# c150_rev_a.net
KiCad netlist of a schematic drawn in EAGLE
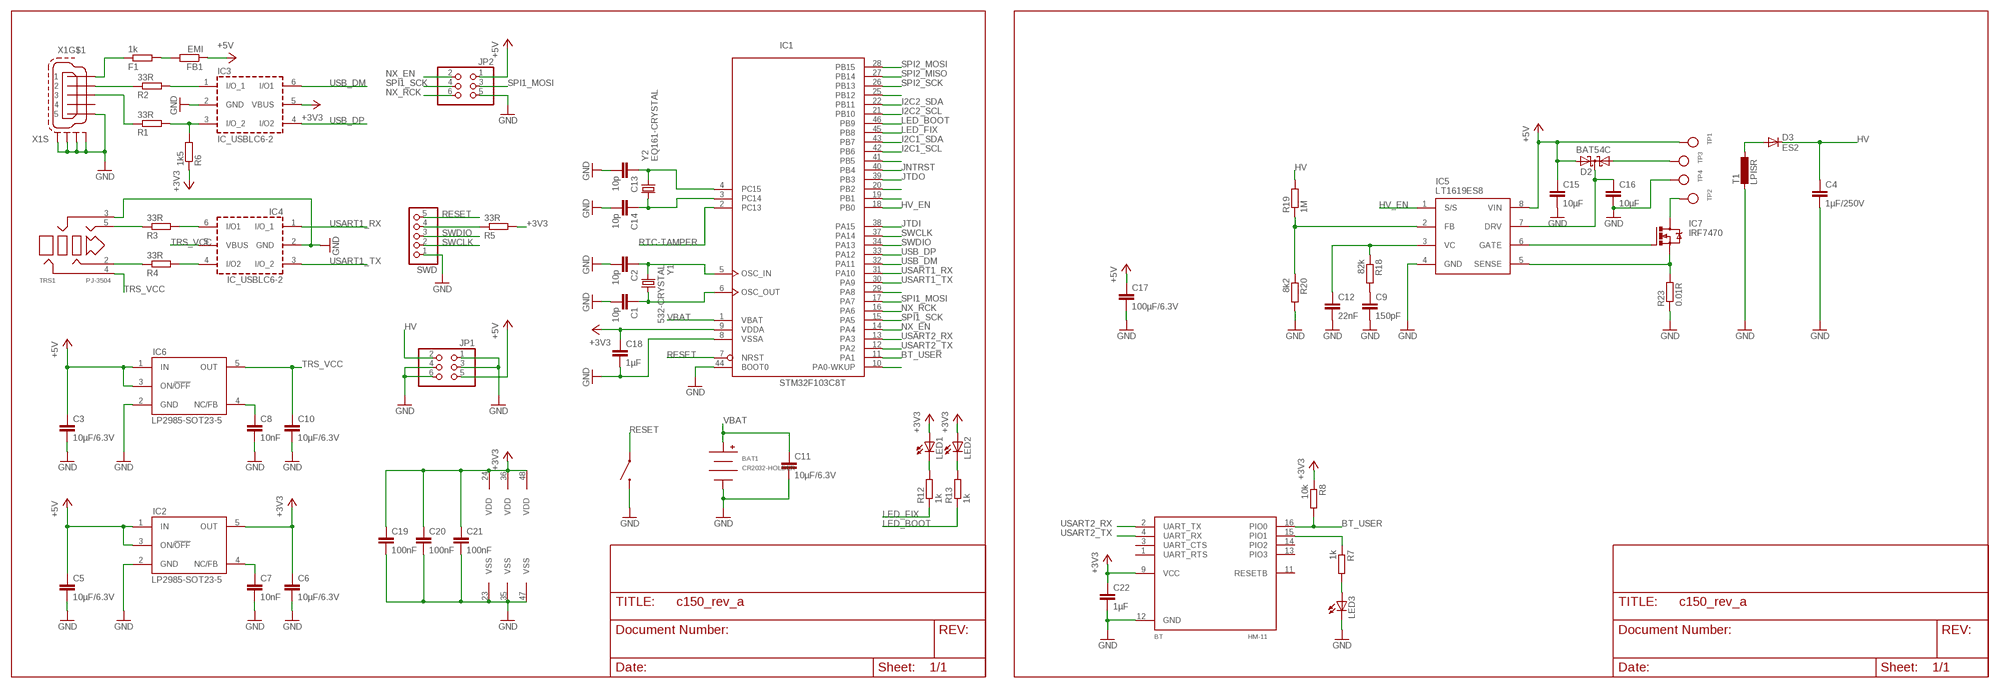
[diagram p0: schematic, sheet 1]

(export (version "E")
  (design (tool "Eeschema 10.0.6"))
  (components
    (comp (ref "BAT1")
      (value "CR2032-HOLDER")
      (footprint "eagle-import:CH28-2032LF")
      (libsource (lib "eagle-import") (part "CR2032-HOLDER"))
    )
    (comp (ref "BT")
      (value "HM-11")
      (footprint "eagle-import:HM-11")
      (libsource (lib "eagle-import") (part "HM-11"))
    )
    (comp (ref "C1")
      (value "10p")
      (footprint "eagle-import:C0603")
      (libsource (lib "eagle-import") (part "C-EUC0603"))
    )
    (comp (ref "C2")
      (value "10p")
      (footprint "eagle-import:C0603")
      (libsource (lib "eagle-import") (part "C-EUC0603"))
    )
    (comp (ref "C3")
      (value "10µF/6.3V")
      (footprint "eagle-import:C0603")
      (libsource (lib "eagle-import") (part "C-EUC0603"))
    )
    (comp (ref "C4")
      (value "1µF/250V")
      (footprint "eagle-import:C2220K")
      (libsource (lib "eagle-import") (part "C-EUC2220K"))
    )
    (comp (ref "C5")
      (value "10µF/6.3V")
      (footprint "eagle-import:C0603")
      (libsource (lib "eagle-import") (part "C-EUC0603"))
    )
    (comp (ref "C6")
      (value "10µF/6.3V")
      (footprint "eagle-import:C0603")
      (libsource (lib "eagle-import") (part "C-EUC0603"))
    )
    (comp (ref "C7")
      (value "10nF")
      (footprint "eagle-import:C0603")
      (libsource (lib "eagle-import") (part "C-EUC0603"))
    )
    (comp (ref "C8")
      (value "10nF")
      (footprint "eagle-import:C0603")
      (libsource (lib "eagle-import") (part "C-EUC0603"))
    )
    (comp (ref "C9")
      (value "150pF")
      (footprint "eagle-import:C0603")
      (libsource (lib "eagle-import") (part "C-EUC0603"))
    )
    (comp (ref "C10")
      (value "10µF/6.3V")
      (footprint "eagle-import:C0603")
      (libsource (lib "eagle-import") (part "C-EUC0603"))
    )
    (comp (ref "C11")
      (value "10µF/6.3V")
      (footprint "eagle-import:C0603")
      (libsource (lib "eagle-import") (part "C-EUC0603"))
    )
    (comp (ref "C12")
      (value "22nF")
      (footprint "eagle-import:C0603")
      (libsource (lib "eagle-import") (part "C-EUC0603"))
    )
    (comp (ref "C13")
      (value "10p")
      (footprint "eagle-import:C0603")
      (libsource (lib "eagle-import") (part "C-EUC0603"))
    )
    (comp (ref "C14")
      (value "10p")
      (footprint "eagle-import:C0603")
      (libsource (lib "eagle-import") (part "C-EUC0603"))
    )
    (comp (ref "C15")
      (value "10µF")
      (footprint "eagle-import:C0603")
      (libsource (lib "eagle-import") (part "C-EUC0603"))
    )
    (comp (ref "C16")
      (value "10µF")
      (footprint "eagle-import:C0603")
      (libsource (lib "eagle-import") (part "C-EUC0603"))
    )
    (comp (ref "C17")
      (value "100µF/6.3V")
      (footprint "eagle-import:C1210")
      (libsource (lib "eagle-import") (part "C-EUC1210"))
    )
    (comp (ref "C18")
      (value "1µF")
      (footprint "eagle-import:C0603")
      (libsource (lib "eagle-import") (part "C-EUC0603"))
    )
    (comp (ref "C19")
      (value "100nF")
      (footprint "eagle-import:C0603")
      (libsource (lib "eagle-import") (part "C-EUC0603"))
    )
    (comp (ref "C20")
      (value "100nF")
      (footprint "eagle-import:C0603")
      (libsource (lib "eagle-import") (part "C-EUC0603"))
    )
    (comp (ref "C21")
      (value "100nF")
      (footprint "eagle-import:C0603")
      (libsource (lib "eagle-import") (part "C-EUC0603"))
    )
    (comp (ref "C22")
      (value "1µF")
      (footprint "eagle-import:C0603")
      (libsource (lib "eagle-import") (part "C-EUC0603"))
    )
    (comp (ref "D2")
      (value "BAT54C")
      (footprint "eagle-import:SOT23")
      (libsource (lib "eagle-import") (part "BAT54C"))
    )
    (comp (ref "D3")
      (value "ES2")
      (footprint "eagle-import:DO-214AA")
      (libsource (lib "eagle-import") (part "ES2"))
    )
    (comp (ref "F1")
      (value "1k")
      (footprint "eagle-import:R0603")
      (libsource (lib "eagle-import") (part "R-EU_R0603"))
    )
    (comp (ref "FB1")
      (value "EMI")
      (footprint "eagle-import:R0603")
      (libsource (lib "eagle-import") (part "R-EU_R0603"))
    )
    (comp (ref "IC1")
      (value "STM32F103C8T")
      (footprint "eagle-import:LQFP48")
      (libsource (lib "eagle-import") (part "STM32F103CT8"))
    )
    (comp (ref "IC2")
      (value "LP2985-SOT23-5")
      (footprint "eagle-import:SOT23-5")
      (libsource (lib "eagle-import") (part "LP2985-SOT23-5"))
    )
    (comp (ref "IC3")
      (value "IC_USBLC6-2")
      (footprint "eagle-import:SOT-23-6L")
      (libsource (lib "eagle-import") (part "IC_USBLC6-2"))
    )
    (comp (ref "IC4")
      (value "IC_USBLC6-2")
      (footprint "eagle-import:SOT-23-6L")
      (libsource (lib "eagle-import") (part "IC_USBLC6-2"))
    )
    (comp (ref "IC5")
      (value "LT1619ES8")
      (footprint "eagle-import:SO8")
      (libsource (lib "eagle-import") (part "LT1619ES8"))
    )
    (comp (ref "IC6")
      (value "LP2985-SOT23-5")
      (footprint "eagle-import:SOT23-5")
      (libsource (lib "eagle-import") (part "LP2985-SOT23-5"))
    )
    (comp (ref "IC7")
      (value "IRF7470")
      (footprint "eagle-import:SO8")
      (libsource (lib "eagle-import") (part "IRF7470"))
    )
    (comp (ref "ISP")
      (value "TACT-SWITCH-40-40")
      (footprint "eagle-import:40-40")
      (libsource (lib "eagle-import") (part "TACT-SWITCH-40-40"))
    )
    (comp (ref "JP1")
      (value "PINHD-2X3_2.54-SMD")
      (footprint "eagle-import:2X03SMD")
      (libsource (lib "eagle-import") (part "PINHD-2X3_2.54-SMD"))
    )
    (comp (ref "JP2")
      (value "PINHD-2X3_2.54-SMD")
      (footprint "eagle-import:2X03SMD")
      (libsource (lib "eagle-import") (part "PINHD-2X3_2.54-SMD"))
    )
    (comp (ref "LED1")
      (value "LEDCHIP-LED0603")
      (footprint "eagle-import:CHIP-LED0603")
      (libsource (lib "eagle-import") (part "LEDCHIP-LED0603"))
    )
    (comp (ref "LED2")
      (value "LEDCHIP-LED0603")
      (footprint "eagle-import:CHIP-LED0603")
      (libsource (lib "eagle-import") (part "LEDCHIP-LED0603"))
    )
    (comp (ref "LED3")
      (value "LEDCHIP-LED0603")
      (footprint "eagle-import:CHIP-LED0603")
      (libsource (lib "eagle-import") (part "LEDCHIP-LED0603"))
    )
    (comp (ref "R1")
      (value "33R")
      (footprint "eagle-import:R0603")
      (libsource (lib "eagle-import") (part "R-EU_R0603"))
    )
    (comp (ref "R2")
      (value "33R")
      (footprint "eagle-import:R0603")
      (libsource (lib "eagle-import") (part "R-EU_R0603"))
    )
    (comp (ref "R3")
      (value "33R")
      (footprint "eagle-import:R0603")
      (libsource (lib "eagle-import") (part "R-EU_R0603"))
    )
    (comp (ref "R4")
      (value "33R")
      (footprint "eagle-import:R0603")
      (libsource (lib "eagle-import") (part "R-EU_R0603"))
    )
    (comp (ref "R5")
      (value "33R")
      (footprint "eagle-import:R0603")
      (libsource (lib "eagle-import") (part "R-EU_R0603"))
    )
    (comp (ref "R6")
      (value "1k5")
      (footprint "eagle-import:R0603")
      (libsource (lib "eagle-import") (part "R-EU_R0603"))
    )
    (comp (ref "R7")
      (value "1k")
      (footprint "eagle-import:R0603")
      (libsource (lib "eagle-import") (part "R-EU_R0603"))
    )
    (comp (ref "R8")
      (value "10k")
      (footprint "eagle-import:R0603")
      (libsource (lib "eagle-import") (part "R-EU_R0603"))
    )
    (comp (ref "R12")
      (value "1k")
      (footprint "eagle-import:R0603")
      (libsource (lib "eagle-import") (part "R-EU_R0603"))
    )
    (comp (ref "R13")
      (value "1k")
      (footprint "eagle-import:R0603")
      (libsource (lib "eagle-import") (part "R-EU_R0603"))
    )
    (comp (ref "R18")
      (value "82k")
      (footprint "eagle-import:R0603")
      (libsource (lib "eagle-import") (part "R-EU_R0603"))
    )
    (comp (ref "R19")
      (value "1M")
      (footprint "eagle-import:M1206")
      (libsource (lib "eagle-import") (part "R-EU_M1206"))
    )
    (comp (ref "R20")
      (value "8k2")
      (footprint "eagle-import:R0603")
      (libsource (lib "eagle-import") (part "R-EU_R0603"))
    )
    (comp (ref "R23")
      (value "0.01R")
      (footprint "eagle-import:R1206")
      (libsource (lib "eagle-import") (part "R-EU_R1206"))
    )
    (comp (ref "SWD")
      (value "HEADER-1X5ROUND")
      (footprint "eagle-import:1X05_ROUND")
      (libsource (lib "eagle-import") (part "HEADER-1X5ROUND"))
    )
    (comp (ref "T1")
      (value "LPISR")
      (footprint "eagle-import:PISR")
      (libsource (lib "eagle-import") (part "LPISR"))
    )
    (comp (ref "TP1")
      (value "TESTPOINTROUND2MM")
      (footprint "eagle-import:TESTPOINT_ROUND_2MM")
      (libsource (lib "eagle-import") (part "TESTPOINTROUND2MM"))
    )
    (comp (ref "TP2")
      (value "TESTPOINTROUND2MM")
      (footprint "eagle-import:TESTPOINT_ROUND_2MM")
      (libsource (lib "eagle-import") (part "TESTPOINTROUND2MM"))
    )
    (comp (ref "TP3")
      (value "TESTPOINTROUND2MM")
      (footprint "eagle-import:TESTPOINT_ROUND_2MM")
      (libsource (lib "eagle-import") (part "TESTPOINTROUND2MM"))
    )
    (comp (ref "TP4")
      (value "TESTPOINTROUND2MM")
      (footprint "eagle-import:TESTPOINT_ROUND_2MM")
      (libsource (lib "eagle-import") (part "TESTPOINTROUND2MM"))
    )
    (comp (ref "TRS1")
      (value "PJ-3504")
      (footprint "eagle-import:YD-PJ-3504")
      (libsource (lib "eagle-import") (part "PJ-3504"))
    )
    (comp (ref "X1")
      (value "MINI-USB-SCHIELD-32005-201")
      (footprint "eagle-import:32005-201")
      (libsource (lib "eagle-import") (part "MINI-USB-SCHIELD-32005-201"))
    )
    (comp (ref "Y1")
      (value "532-CRYSTAL")
      (footprint "eagle-import:2PIN50X32")
      (libsource (lib "eagle-import") (part "532-CRYSTAL"))
    )
    (comp (ref "Y2")
      (value "EQ161-CRYSTAL")
      (footprint "eagle-import:EQ161")
      (libsource (lib "eagle-import") (part "EQ161-CRYSTAL"))
    )
  )
  (nets
    (net (code "1") (name "+3V3") (class "Default")
      (node (ref "BT") (pin "9") (pinfunction "VCC_9") (pintype "bidirectional"))
      (node (ref "C18") (pin "1") (pinfunction "1_1") (pintype "passive"))
      (node (ref "C19") (pin "1") (pinfunction "1_1") (pintype "passive"))
      (node (ref "C20") (pin "1") (pinfunction "1_1") (pintype "passive"))
      (node (ref "C21") (pin "1") (pinfunction "1_1") (pintype "passive"))
      (node (ref "C22") (pin "1") (pinfunction "1_1") (pintype "passive"))
      (node (ref "C6") (pin "1") (pinfunction "1_1") (pintype "passive"))
      (node (ref "IC1") (pin "24") (pinfunction "VDD_24") (pintype "power_in"))
      (node (ref "IC1") (pin "36") (pinfunction "VDD_36") (pintype "power_in"))
      (node (ref "IC1") (pin "48") (pinfunction "VDD_48") (pintype "power_in"))
      (node (ref "IC1") (pin "9") (pinfunction "VDDA_9") (pintype "power_in"))
      (node (ref "IC2") (pin "5") (pinfunction "OUT_5") (pintype "bidirectional"))
      (node (ref "IC3") (pin "5") (pinfunction "VBUS_5") (pintype "bidirectional"))
      (node (ref "LED1") (pin "A") (pinfunction "A_A") (pintype "passive"))
      (node (ref "LED2") (pin "A") (pinfunction "A_A") (pintype "passive"))
      (node (ref "R5") (pin "2") (pinfunction "2_2") (pintype "passive"))
      (node (ref "R6") (pin "1") (pinfunction "1_1") (pintype "passive"))
      (node (ref "R8") (pin "1") (pinfunction "1_1") (pintype "passive"))
    )
    (net (code "2") (name "+5V") (class "Default")
      (node (ref "C15") (pin "1") (pinfunction "1_1") (pintype "passive"))
      (node (ref "C17") (pin "1") (pinfunction "1_1") (pintype "passive"))
      (node (ref "C3") (pin "1") (pinfunction "1_1") (pintype "passive"))
      (node (ref "C5") (pin "1") (pinfunction "1_1") (pintype "passive"))
      (node (ref "D2") (pin "2") (pinfunction "A2_2") (pintype "passive"))
      (node (ref "FB1") (pin "1") (pinfunction "1_1") (pintype "passive"))
      (node (ref "IC2") (pin "1") (pinfunction "IN_1") (pintype "bidirectional"))
      (node (ref "IC2") (pin "3") (pinfunction "ON/~{OFF}_3") (pintype "bidirectional"))
      (node (ref "IC5") (pin "8") (pinfunction "VIN_8") (pintype "bidirectional"))
      (node (ref "IC6") (pin "1") (pinfunction "IN_1") (pintype "bidirectional"))
      (node (ref "IC6") (pin "3") (pinfunction "ON/~{OFF}_3") (pintype "bidirectional"))
      (node (ref "JP1") (pin "5") (pinfunction "5_5") (pintype "passive"))
      (node (ref "JP2") (pin "1") (pinfunction "1_1") (pintype "passive"))
      (node (ref "TP1") (pin "P$1") (pinfunction "P$1_P$1") (pintype "bidirectional"))
    )
    (net (code "3") (name "/BT_USER") (class "Default")
      (node (ref "BT") (pin "16") (pinfunction "PIO0_16") (pintype "bidirectional"))
      (node (ref "IC1") (pin "11") (pinfunction "PA1_11") (pintype "bidirectional"))
      (node (ref "R8") (pin "2") (pinfunction "2_2") (pintype "passive"))
    )
    (net (code "4") (name "/HV") (class "Default")
      (node (ref "C4") (pin "1") (pinfunction "1_1") (pintype "passive"))
      (node (ref "D3") (pin "C") (pinfunction "C_C") (pintype "passive"))
      (node (ref "JP1") (pin "2") (pinfunction "2_2") (pintype "passive"))
      (node (ref "R19") (pin "2") (pinfunction "2_2") (pintype "passive"))
    )
    (net (code "5") (name "/HV_EN") (class "Default")
      (node (ref "IC1") (pin "18") (pinfunction "PB0_18") (pintype "bidirectional"))
      (node (ref "IC5") (pin "1") (pinfunction "S/S_1") (pintype "bidirectional"))
    )
    (net (code "6") (name "/I2C1_SCL") (class "Default")
      (node (ref "IC1") (pin "42") (pinfunction "PB6_42") (pintype "bidirectional"))
    )
    (net (code "7") (name "/I2C1_SDA") (class "Default")
      (node (ref "IC1") (pin "43") (pinfunction "PB7_43") (pintype "bidirectional"))
    )
    (net (code "8") (name "/I2C2_SCL") (class "Default")
      (node (ref "IC1") (pin "21") (pinfunction "PB10_21") (pintype "bidirectional"))
    )
    (net (code "9") (name "/I2C2_SDA") (class "Default")
      (node (ref "IC1") (pin "22") (pinfunction "PB11_22") (pintype "bidirectional"))
    )
    (net (code "10") (name "/JNTRST") (class "Default")
      (node (ref "IC1") (pin "40") (pinfunction "PB4_40") (pintype "bidirectional"))
    )
    (net (code "11") (name "/JTDI") (class "Default")
      (node (ref "IC1") (pin "38") (pinfunction "PA15_38") (pintype "bidirectional"))
    )
    (net (code "12") (name "/JTDO") (class "Default")
      (node (ref "IC1") (pin "39") (pinfunction "PB3_39") (pintype "bidirectional"))
    )
    (net (code "13") (name "/LED_BOOT") (class "Default")
      (node (ref "IC1") (pin "46") (pinfunction "PB9_46") (pintype "bidirectional"))
      (node (ref "R13") (pin "1") (pinfunction "1_1") (pintype "passive"))
    )
    (net (code "14") (name "/LED_FIX") (class "Default")
      (node (ref "IC1") (pin "45") (pinfunction "PB8_45") (pintype "bidirectional"))
      (node (ref "R12") (pin "1") (pinfunction "1_1") (pintype "passive"))
    )
    (net (code "15") (name "/NX_EN") (class "Default")
      (node (ref "IC1") (pin "14") (pinfunction "PA4_14") (pintype "bidirectional"))
      (node (ref "JP2") (pin "2") (pinfunction "2_2") (pintype "passive"))
    )
    (net (code "16") (name "/NX_RCK") (class "Default")
      (node (ref "IC1") (pin "16") (pinfunction "PA6_16") (pintype "bidirectional"))
      (node (ref "JP2") (pin "6") (pinfunction "6_6") (pintype "passive"))
    )
    (net (code "17") (name "/RESET") (class "Default")
      (node (ref "IC1") (pin "7") (pinfunction "NRST_7") (pintype "bidirectional"))
      (node (ref "ISP") (pin "3") (pinfunction "P$2_3") (pintype "bidirectional"))
      (node (ref "ISP") (pin "4") (pinfunction "P$2_4") (pintype "bidirectional"))
      (node (ref "SWD") (pin "5") (pinfunction "5_5") (pintype "passive"))
    )
    (net (code "18") (name "/RTC-TAMPER") (class "Default")
      (node (ref "IC1") (pin "2") (pinfunction "PC13_2") (pintype "bidirectional"))
    )
    (net (code "19") (name "/SPI1_MOSI") (class "Default")
      (node (ref "IC1") (pin "17") (pinfunction "PA7_17") (pintype "bidirectional"))
      (node (ref "JP2") (pin "3") (pinfunction "3_3") (pintype "passive"))
    )
    (net (code "20") (name "/SPI1_SCK") (class "Default")
      (node (ref "IC1") (pin "15") (pinfunction "PA5_15") (pintype "bidirectional"))
      (node (ref "JP2") (pin "4") (pinfunction "4_4") (pintype "passive"))
    )
    (net (code "21") (name "/SPI2_MISO") (class "Default")
      (node (ref "IC1") (pin "27") (pinfunction "PB14_27") (pintype "bidirectional"))
    )
    (net (code "22") (name "/SPI2_MOSI") (class "Default")
      (node (ref "IC1") (pin "28") (pinfunction "PB15_28") (pintype "bidirectional"))
    )
    (net (code "23") (name "/SPI2_SCK") (class "Default")
      (node (ref "IC1") (pin "26") (pinfunction "PB13_26") (pintype "bidirectional"))
    )
    (net (code "24") (name "/SWCLK") (class "Default")
      (node (ref "IC1") (pin "37") (pinfunction "PA14_37") (pintype "bidirectional"))
      (node (ref "SWD") (pin "2") (pinfunction "2_2") (pintype "passive"))
    )
    (net (code "25") (name "/SWDIO") (class "Default")
      (node (ref "IC1") (pin "34") (pinfunction "PA13_34") (pintype "bidirectional"))
      (node (ref "SWD") (pin "3") (pinfunction "3_3") (pintype "passive"))
    )
    (net (code "26") (name "/TRS_VCC") (class "Default")
      (node (ref "C10") (pin "1") (pinfunction "1_1") (pintype "passive"))
      (node (ref "IC4") (pin "5") (pinfunction "VBUS_5") (pintype "bidirectional"))
      (node (ref "IC6") (pin "5") (pinfunction "OUT_5") (pintype "bidirectional"))
      (node (ref "TRS1") (pin "4") (pinfunction "4_4") (pintype "bidirectional"))
    )
    (net (code "27") (name "/USART1_RX") (class "Default")
      (node (ref "IC1") (pin "31") (pinfunction "PA10_31") (pintype "bidirectional"))
      (node (ref "IC4") (pin "1") (pinfunction "I/O_1_1") (pintype "bidirectional"))
    )
    (net (code "28") (name "/USART1_TX") (class "Default")
      (node (ref "IC1") (pin "30") (pinfunction "PA9_30") (pintype "bidirectional"))
      (node (ref "IC4") (pin "3") (pinfunction "I/O_2_3") (pintype "bidirectional"))
    )
    (net (code "29") (name "/USART2_RX") (class "Default")
      (node (ref "BT") (pin "2") (pinfunction "UART_TX_2") (pintype "bidirectional"))
      (node (ref "IC1") (pin "13") (pinfunction "PA3_13") (pintype "bidirectional"))
    )
    (net (code "30") (name "/USART2_TX") (class "Default")
      (node (ref "BT") (pin "4") (pinfunction "UART_RX_4") (pintype "bidirectional"))
      (node (ref "IC1") (pin "12") (pinfunction "PA2_12") (pintype "bidirectional"))
    )
    (net (code "31") (name "/USB_DM") (class "Default")
      (node (ref "IC1") (pin "32") (pinfunction "PA11_32") (pintype "bidirectional"))
      (node (ref "IC3") (pin "6") (pinfunction "I/O1_6") (pintype "bidirectional"))
    )
    (net (code "32") (name "/USB_DP") (class "Default")
      (node (ref "IC1") (pin "33") (pinfunction "PA12_33") (pintype "bidirectional"))
      (node (ref "IC3") (pin "4") (pinfunction "I/O2_4") (pintype "bidirectional"))
    )
    (net (code "33") (name "/VBAT") (class "Default")
      (node (ref "BAT1") (pin "POS") (pinfunction "POS_POS") (pintype "bidirectional"))
      (node (ref "C11") (pin "1") (pinfunction "1_1") (pintype "passive"))
      (node (ref "IC1") (pin "1") (pinfunction "VBAT_1") (pintype "power_in"))
    )
    (net (code "34") (name "GND") (class "Default")
      (node (ref "BAT1") (pin "NEG") (pinfunction "NEG_NEG") (pintype "bidirectional"))
      (node (ref "BT") (pin "12") (pinfunction "GND_12") (pintype "bidirectional"))
      (node (ref "C1") (pin "2") (pinfunction "2_2") (pintype "passive"))
      (node (ref "C10") (pin "2") (pinfunction "2_2") (pintype "passive"))
      (node (ref "C11") (pin "2") (pinfunction "2_2") (pintype "passive"))
      (node (ref "C12") (pin "2") (pinfunction "2_2") (pintype "passive"))
      (node (ref "C13") (pin "2") (pinfunction "2_2") (pintype "passive"))
      (node (ref "C14") (pin "2") (pinfunction "2_2") (pintype "passive"))
      (node (ref "C15") (pin "2") (pinfunction "2_2") (pintype "passive"))
      (node (ref "C16") (pin "2") (pinfunction "2_2") (pintype "passive"))
      (node (ref "C17") (pin "2") (pinfunction "2_2") (pintype "passive"))
      (node (ref "C18") (pin "2") (pinfunction "2_2") (pintype "passive"))
      (node (ref "C19") (pin "2") (pinfunction "2_2") (pintype "passive"))
      (node (ref "C2") (pin "2") (pinfunction "2_2") (pintype "passive"))
      (node (ref "C20") (pin "2") (pinfunction "2_2") (pintype "passive"))
      (node (ref "C21") (pin "2") (pinfunction "2_2") (pintype "passive"))
      (node (ref "C22") (pin "2") (pinfunction "2_2") (pintype "passive"))
      (node (ref "C3") (pin "2") (pinfunction "2_2") (pintype "passive"))
      (node (ref "C4") (pin "2") (pinfunction "2_2") (pintype "passive"))
      (node (ref "C5") (pin "2") (pinfunction "2_2") (pintype "passive"))
      (node (ref "C6") (pin "2") (pinfunction "2_2") (pintype "passive"))
      (node (ref "C7") (pin "2") (pinfunction "2_2") (pintype "passive"))
      (node (ref "C8") (pin "2") (pinfunction "2_2") (pintype "passive"))
      (node (ref "C9") (pin "2") (pinfunction "2_2") (pintype "passive"))
      (node (ref "IC1") (pin "23") (pinfunction "VSS_23") (pintype "power_in"))
      (node (ref "IC1") (pin "35") (pinfunction "VSS_35") (pintype "power_in"))
      (node (ref "IC1") (pin "44") (pinfunction "BOOT0_44") (pintype "input"))
      (node (ref "IC1") (pin "47") (pinfunction "VSS_47") (pintype "power_in"))
      (node (ref "IC1") (pin "8") (pinfunction "VSSA_8") (pintype "power_in"))
      (node (ref "IC2") (pin "2") (pinfunction "GND_2") (pintype "bidirectional"))
      (node (ref "IC3") (pin "2") (pinfunction "GND_2") (pintype "bidirectional"))
      (node (ref "IC4") (pin "2") (pinfunction "GND_2") (pintype "bidirectional"))
      (node (ref "IC5") (pin "4") (pinfunction "GND_4") (pintype "bidirectional"))
      (node (ref "IC6") (pin "2") (pinfunction "GND_2") (pintype "bidirectional"))
      (node (ref "ISP") (pin "1") (pinfunction "P$1_1") (pintype "bidirectional"))
      (node (ref "ISP") (pin "2") (pinfunction "P$1_2") (pintype "bidirectional"))
      (node (ref "JP1") (pin "1") (pinfunction "1_1") (pintype "passive"))
      (node (ref "JP1") (pin "3") (pinfunction "3_3") (pintype "passive"))
      (node (ref "JP1") (pin "4") (pinfunction "4_4") (pintype "passive"))
      (node (ref "JP1") (pin "6") (pinfunction "6_6") (pintype "passive"))
      (node (ref "JP2") (pin "5") (pinfunction "5_5") (pintype "passive"))
      (node (ref "LED3") (pin "C") (pinfunction "C_C") (pintype "passive"))
      (node (ref "R20") (pin "2") (pinfunction "2_2") (pintype "passive"))
      (node (ref "R23") (pin "1") (pinfunction "1_1") (pintype "passive"))
      (node (ref "SWD") (pin "1") (pinfunction "1_1") (pintype "passive"))
      (node (ref "T1") (pin "P$2") (pinfunction "2_P$2") (pintype "passive"))
      (node (ref "TP4") (pin "P$1") (pinfunction "P$1_P$1") (pintype "bidirectional"))
      (node (ref "TRS1") (pin "3") (pinfunction "3_3") (pintype "bidirectional"))
      (node (ref "X1") (pin "5") (pinfunction "5_5") (pintype "passive"))
      (node (ref "X1") (pin "M1") (pinfunction "S1_M1") (pintype "passive"))
      (node (ref "X1") (pin "M2") (pinfunction "S2_M2") (pintype "passive"))
      (node (ref "X1") (pin "M3") (pinfunction "S3_M3") (pintype "passive"))
      (node (ref "X1") (pin "M4") (pinfunction "S4_M4") (pintype "passive"))
    )
    (net (code "35") (name "Net-(BT-PIO1)") (class "Default")
      (node (ref "BT") (pin "15") (pinfunction "PIO1_15") (pintype "bidirectional"))
      (node (ref "R7") (pin "1") (pinfunction "1_1") (pintype "passive"))
    )
    (net (code "36") (name "Net-(C9-Pad1)") (class "Default")
      (node (ref "C9") (pin "1") (pinfunction "1_1") (pintype "passive"))
      (node (ref "R18") (pin "2") (pinfunction "2_2") (pintype "passive"))
    )
    (net (code "37") (name "Net-(D2-A1)") (class "Default")
      (node (ref "D2") (pin "1") (pinfunction "A1_1") (pintype "passive"))
      (node (ref "TP3") (pin "P$1") (pinfunction "P$1_P$1") (pintype "bidirectional"))
    )
    (net (code "38") (name "Net-(D2-CC)") (class "Default")
      (node (ref "C16") (pin "1") (pinfunction "1_1") (pintype "passive"))
      (node (ref "D2") (pin "3") (pinfunction "CC_3") (pintype "passive"))
      (node (ref "IC5") (pin "7") (pinfunction "DRV_7") (pintype "bidirectional"))
    )
    (net (code "39") (name "Net-(F1-Pad1)") (class "Default")
      (node (ref "F1") (pin "1") (pinfunction "1_1") (pintype "passive"))
      (node (ref "X1") (pin "1") (pinfunction "1_1") (pintype "passive"))
    )
    (net (code "40") (name "Net-(F1-Pad2)") (class "Default")
      (node (ref "F1") (pin "2") (pinfunction "2_2") (pintype "passive"))
      (node (ref "FB1") (pin "2") (pinfunction "2_2") (pintype "passive"))
    )
    (net (code "41") (name "Net-(IC1A-OSC_IN)") (class "Default")
      (node (ref "C2") (pin "1") (pinfunction "1_1") (pintype "passive"))
      (node (ref "IC1") (pin "5") (pinfunction "OSC_IN_5") (pintype "bidirectional"))
      (node (ref "Y1") (pin "P$2") (pinfunction "2_P$2") (pintype "passive"))
    )
    (net (code "42") (name "Net-(IC1A-OSC_OUT)") (class "Default")
      (node (ref "C1") (pin "1") (pinfunction "1_1") (pintype "passive"))
      (node (ref "IC1") (pin "6") (pinfunction "OSC_OUT_6") (pintype "bidirectional"))
      (node (ref "Y1") (pin "P$1") (pinfunction "1_P$1") (pintype "passive"))
    )
    (net (code "43") (name "Net-(IC1A-PC14)") (class "Default")
      (node (ref "C14") (pin "1") (pinfunction "1_1") (pintype "passive"))
      (node (ref "IC1") (pin "3") (pinfunction "PC14_3") (pintype "bidirectional"))
      (node (ref "Y2") (pin "P$2") (pinfunction "2_P$2") (pintype "passive"))
    )
    (net (code "44") (name "Net-(IC1A-PC15)") (class "Default")
      (node (ref "C13") (pin "1") (pinfunction "1_1") (pintype "passive"))
      (node (ref "IC1") (pin "4") (pinfunction "PC15_4") (pintype "bidirectional"))
      (node (ref "Y2") (pin "P$1") (pinfunction "1_P$1") (pintype "passive"))
    )
    (net (code "45") (name "Net-(IC2-NC{slash}FB)") (class "Default")
      (node (ref "C7") (pin "1") (pinfunction "1_1") (pintype "passive"))
      (node (ref "IC2") (pin "4") (pinfunction "NC/FB_4") (pintype "bidirectional"))
    )
    (net (code "46") (name "Net-(IC3-I{slash}O_1)") (class "Default")
      (node (ref "IC3") (pin "1") (pinfunction "I/O_1_1") (pintype "bidirectional"))
      (node (ref "R2") (pin "2") (pinfunction "2_2") (pintype "passive"))
    )
    (net (code "47") (name "Net-(IC3-I{slash}O_2)") (class "Default")
      (node (ref "IC3") (pin "3") (pinfunction "I/O_2_3") (pintype "bidirectional"))
      (node (ref "R1") (pin "2") (pinfunction "2_2") (pintype "passive"))
      (node (ref "R6") (pin "2") (pinfunction "2_2") (pintype "passive"))
    )
    (net (code "48") (name "Net-(IC4-I{slash}O1)") (class "Default")
      (node (ref "IC4") (pin "6") (pinfunction "I/O1_6") (pintype "bidirectional"))
      (node (ref "R3") (pin "2") (pinfunction "2_2") (pintype "passive"))
    )
    (net (code "49") (name "Net-(IC4-I{slash}O2)") (class "Default")
      (node (ref "IC4") (pin "4") (pinfunction "I/O2_4") (pintype "bidirectional"))
      (node (ref "R4") (pin "2") (pinfunction "2_2") (pintype "passive"))
    )
    (net (code "50") (name "Net-(IC5-FB)") (class "Default")
      (node (ref "IC5") (pin "2") (pinfunction "FB_2") (pintype "bidirectional"))
      (node (ref "R19") (pin "1") (pinfunction "1_1") (pintype "passive"))
      (node (ref "R20") (pin "1") (pinfunction "1_1") (pintype "passive"))
    )
    (net (code "51") (name "Net-(IC5-GATE)") (class "Default")
      (node (ref "IC5") (pin "6") (pinfunction "GATE_6") (pintype "bidirectional"))
      (node (ref "IC7") (pin "4") (pinfunction "G_4") (pintype "passive"))
    )
    (net (code "52") (name "Net-(IC5-SENSE)") (class "Default")
      (node (ref "IC5") (pin "5") (pinfunction "SENSE_5") (pintype "bidirectional"))
      (node (ref "IC7") (pin "1") (pinfunction "S_1") (pintype "passive"))
      (node (ref "IC7") (pin "2") (pinfunction "S_2") (pintype "passive"))
      (node (ref "IC7") (pin "3") (pinfunction "S_3") (pintype "passive"))
      (node (ref "R23") (pin "2") (pinfunction "2_2") (pintype "passive"))
    )
    (net (code "53") (name "Net-(IC5-VC)") (class "Default")
      (node (ref "C12") (pin "1") (pinfunction "1_1") (pintype "passive"))
      (node (ref "IC5") (pin "3") (pinfunction "VC_3") (pintype "bidirectional"))
      (node (ref "R18") (pin "1") (pinfunction "1_1") (pintype "passive"))
    )
    (net (code "54") (name "Net-(IC6-NC{slash}FB)") (class "Default")
      (node (ref "C8") (pin "1") (pinfunction "1_1") (pintype "passive"))
      (node (ref "IC6") (pin "4") (pinfunction "NC/FB_4") (pintype "bidirectional"))
    )
    (net (code "55") (name "Net-(IC7-D-Pad5)") (class "Default")
      (node (ref "IC7") (pin "5") (pinfunction "D_5") (pintype "passive"))
      (node (ref "IC7") (pin "6") (pinfunction "D_6") (pintype "passive"))
      (node (ref "IC7") (pin "7") (pinfunction "D_7") (pintype "passive"))
      (node (ref "IC7") (pin "8") (pinfunction "D_8") (pintype "passive"))
      (node (ref "TP2") (pin "P$1") (pinfunction "P$1_P$1") (pintype "bidirectional"))
    )
    (net (code "56") (name "Net-(LED1-PadC)") (class "Default")
      (node (ref "LED1") (pin "C") (pinfunction "C_C") (pintype "passive"))
      (node (ref "R12") (pin "2") (pinfunction "2_2") (pintype "passive"))
    )
    (net (code "57") (name "Net-(LED2-PadC)") (class "Default")
      (node (ref "LED2") (pin "C") (pinfunction "C_C") (pintype "passive"))
      (node (ref "R13") (pin "2") (pinfunction "2_2") (pintype "passive"))
    )
    (net (code "58") (name "Net-(LED3-PadA)") (class "Default")
      (node (ref "LED3") (pin "A") (pinfunction "A_A") (pintype "passive"))
      (node (ref "R7") (pin "2") (pinfunction "2_2") (pintype "passive"))
    )
    (net (code "59") (name "Net-(R1-Pad1)") (class "Default")
      (node (ref "R1") (pin "1") (pinfunction "1_1") (pintype "passive"))
      (node (ref "X1") (pin "3") (pinfunction "3_3") (pintype "passive"))
    )
    (net (code "60") (name "Net-(R2-Pad1)") (class "Default")
      (node (ref "R2") (pin "1") (pinfunction "1_1") (pintype "passive"))
      (node (ref "X1") (pin "2") (pinfunction "2_2") (pintype "passive"))
    )
    (net (code "61") (name "Net-(R3-Pad1)") (class "Default")
      (node (ref "R3") (pin "1") (pinfunction "1_1") (pintype "passive"))
      (node (ref "TRS1") (pin "5") (pinfunction "5_5") (pintype "bidirectional"))
    )
    (net (code "62") (name "Net-(R4-Pad1)") (class "Default")
      (node (ref "R4") (pin "1") (pinfunction "1_1") (pintype "passive"))
      (node (ref "TRS1") (pin "2") (pinfunction "2_2") (pintype "bidirectional"))
    )
    (net (code "63") (name "Net-(R5-Pad1)") (class "Default")
      (node (ref "R5") (pin "1") (pinfunction "1_1") (pintype "passive"))
      (node (ref "SWD") (pin "4") (pinfunction "4_4") (pintype "passive"))
    )
    (net (code "64") (name "Net-(T1-1)") (class "Default")
      (node (ref "D3") (pin "A") (pinfunction "A_A") (pintype "passive"))
      (node (ref "T1") (pin "P$1") (pinfunction "1_P$1") (pintype "passive"))
    )
    (net (code "65") (name "unconnected-(BT-PIO2-Pad14)") (class "Default")
      (node (ref "BT") (pin "14") (pinfunction "PIO2_14") (pintype "bidirectional"))
    )
    (net (code "66") (name "unconnected-(BT-PIO3-Pad13)") (class "Default")
      (node (ref "BT") (pin "13") (pinfunction "PIO3_13") (pintype "bidirectional"))
    )
    (net (code "67") (name "unconnected-(BT-RESETB-Pad11)") (class "Default")
      (node (ref "BT") (pin "11") (pinfunction "RESETB_11") (pintype "bidirectional"))
    )
    (net (code "68") (name "unconnected-(BT-UART_CTS-Pad3)") (class "Default")
      (node (ref "BT") (pin "3") (pinfunction "UART_CTS_3") (pintype "bidirectional"))
    )
    (net (code "69") (name "unconnected-(BT-UART_RTS-Pad1)") (class "Default")
      (node (ref "BT") (pin "1") (pinfunction "UART_RTS_1") (pintype "bidirectional"))
    )
    (net (code "70") (name "unconnected-(IC1A-PA0-WKUP-Pad10)") (class "Default")
      (node (ref "IC1") (pin "10") (pinfunction "PA0-WKUP_10") (pintype "bidirectional"))
    )
    (net (code "71") (name "unconnected-(IC1A-PA8-Pad29)") (class "Default")
      (node (ref "IC1") (pin "29") (pinfunction "PA8_29") (pintype "bidirectional"))
    )
    (net (code "72") (name "unconnected-(IC1A-PB1-Pad19)") (class "Default")
      (node (ref "IC1") (pin "19") (pinfunction "PB1_19") (pintype "bidirectional"))
    )
    (net (code "73") (name "unconnected-(IC1A-PB2-Pad20)") (class "Default")
      (node (ref "IC1") (pin "20") (pinfunction "PB2_20") (pintype "bidirectional"))
    )
    (net (code "74") (name "unconnected-(IC1A-PB5-Pad41)") (class "Default")
      (node (ref "IC1") (pin "41") (pinfunction "PB5_41") (pintype "bidirectional"))
    )
    (net (code "75") (name "unconnected-(IC1A-PB12-Pad25)") (class "Default")
      (node (ref "IC1") (pin "25") (pinfunction "PB12_25") (pintype "bidirectional"))
    )
    (net (code "76") (name "unconnected-(X1-Pad4)") (class "Default")
      (node (ref "X1") (pin "4") (pinfunction "4_4") (pintype "passive"))
    )
  )
)
